# MCU.net
KiCad netlist of a schematic drawn in Altium Designer
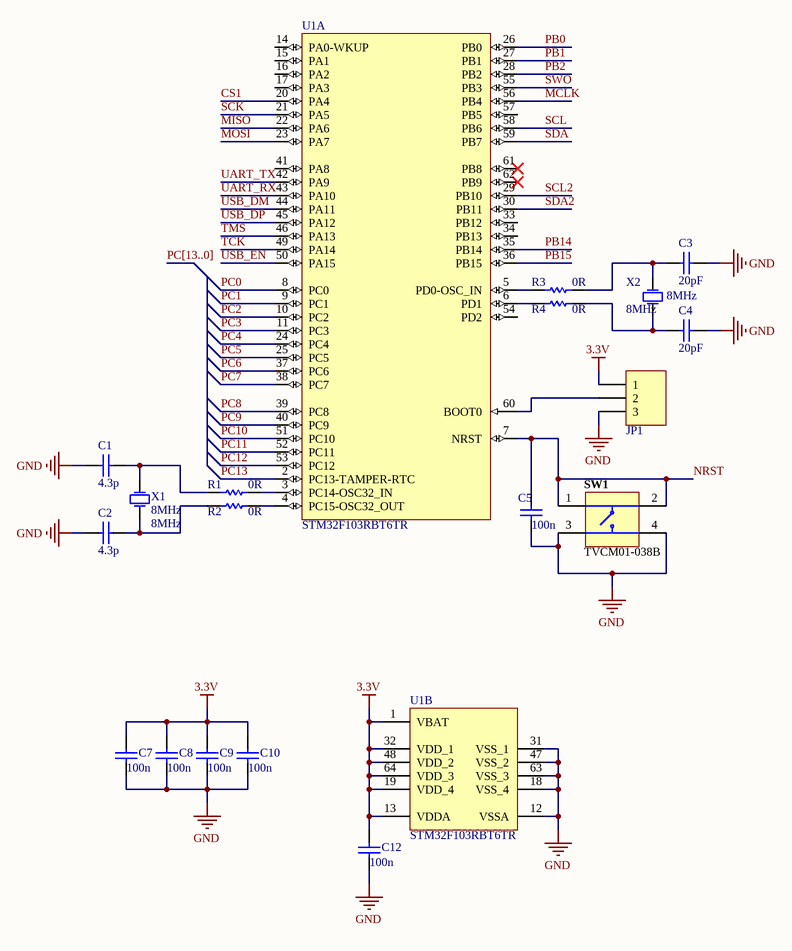
[diagram p0: MCU.SchDoc]

(export (version "E")
  (design (tool "Eeschema 10.0.6"))
  (components
    (comp (ref "C1")
      (value "4.3p")
      (footprint "CAPC0603(1608)100_L")
      (description "0603 (1608 Metric) Chip Capacitor")
      (libsource (lib "Altium Content Vault") (part "CAP_5"))
    )
    (comp (ref "C2")
      (value "4.3p")
      (footprint "CAPC0603(1608)100_L")
      (description "0603 (1608 Metric) Chip Capacitor")
      (libsource (lib "Altium Content Vault") (part "CAP_5"))
    )
    (comp (ref "C3")
      (value "20pF")
      (footprint "CAPC0603(1608)100_L")
      (description "0603 (1608 Metric) Chip Capacitor")
      (libsource (lib "Altium Content Vault") (part "CAP_5"))
    )
    (comp (ref "C4")
      (value "20pF")
      (footprint "CAPC0603(1608)100_L")
      (description "0603 (1608 Metric) Chip Capacitor")
      (libsource (lib "Altium Content Vault") (part "CAP_5"))
    )
    (comp (ref "C5")
      (value "100n")
      (footprint "CAPC0603(1608)100_L")
      (description "0603 (1608 Metric) Chip Capacitor")
      (libsource (lib "Altium Content Vault") (part "CAP_5"))
    )
    (comp (ref "C7")
      (value "100n")
      (footprint "CAPC0603(1608)100_L")
      (description "0603 (1608 Metric) Chip Capacitor")
      (libsource (lib "Altium Content Vault") (part "CAP_5"))
    )
    (comp (ref "C8")
      (value "100n")
      (footprint "CAPC0603(1608)100_L")
      (description "0603 (1608 Metric) Chip Capacitor")
      (libsource (lib "Altium Content Vault") (part "CAP_5"))
    )
    (comp (ref "C9")
      (value "100n")
      (footprint "CAPC0603(1608)100_L")
      (description "0603 (1608 Metric) Chip Capacitor")
      (libsource (lib "Altium Content Vault") (part "CAP_5"))
    )
    (comp (ref "C10")
      (value "100n")
      (footprint "CAPC0603(1608)100_L")
      (description "0603 (1608 Metric) Chip Capacitor")
      (libsource (lib "Altium Content Vault") (part "CAP_5"))
    )
    (comp (ref "C12")
      (value "100n")
      (footprint "CAPC0603(1608)100_L")
      (description "0603 (1608 Metric) Chip Capacitor")
      (libsource (lib "Altium Content Vault") (part "CAP_5"))
    )
    (comp (ref "JP1")
      (value "HDR1X3")
      (footprint "HDR1X3")
      (description "Header, 3-Pin")
      (fields (field (name "PUBLISHER") "Altium Limited"))
      (libsource (lib "Library_Altium") (part "HDR1X3"))
    )
    (comp (ref "R1")
      (value "0R")
      (footprint "RESC0603(1608)_L")
      (description "0603 (1608 Metric) Chip Resistor")
      (libsource (lib "Altium Content Vault") (part "RES_3"))
    )
    (comp (ref "R2")
      (value "0R")
      (footprint "RESC0603(1608)_L")
      (description "0603 (1608 Metric) Chip Resistor")
      (libsource (lib "Altium Content Vault") (part "RES_3"))
    )
    (comp (ref "R3")
      (value "0R")
      (footprint "RESC0603(1608)_L")
      (description "0603 (1608 Metric) Chip Resistor")
      (libsource (lib "Altium Content Vault") (part "RES_3"))
    )
    (comp (ref "R4")
      (value "0R")
      (footprint "RESC0603(1608)_L")
      (description "0603 (1608 Metric) Chip Resistor")
      (libsource (lib "Altium Content Vault") (part "RES_3"))
    )
    (comp (ref "SW1")
      (value "TVCM01-038B")
      (footprint "JNFU-TVCM01-038B_V")
      (description "Switch, Push Button, 50 mA, 12V DC, SMD")
      (libsource (lib "Altium Content Vault") (part "JNFU-TVCM01-038B-4"))
    )
    (comp (ref "U1")
      (value "STM32F103RBT6TR")
      (footprint "LQFP64_N")
      (libsource (lib "Altium Content Vault") (part "MC-ARM-STM32F101-SQ64"))
    )
    (comp (ref "X1")
      (value "8MHz")
      (footprint "HC49/4H_SMX")
      (description "Oscillator")
      (fields (field (name "ALTIUM_VALUE") "8MHz"))
      (libsource (lib "Library_Altium") (part "XTAL"))
    )
    (comp (ref "X2")
      (value "8MHz")
      (footprint "HC49/4H_SMX")
      (description "Oscillator")
      (fields (field (name "ALTIUM_VALUE") "8MHz"))
      (libsource (lib "Library_Altium") (part "XTAL"))
    )
  )
  (nets
    (net (code "1") (name "/CS1") (class "Default")
      (node (ref "U1") (pin "20") (pinfunction "PA4_20") (pintype "bidirectional"))
    )
    (net (code "2") (name "/MCLK") (class "Default")
      (node (ref "U1") (pin "56") (pinfunction "PB4_56") (pintype "bidirectional"))
    )
    (net (code "3") (name "/MISO") (class "Default")
      (node (ref "U1") (pin "22") (pinfunction "PA6_22") (pintype "bidirectional"))
    )
    (net (code "4") (name "/MOSI") (class "Default")
      (node (ref "U1") (pin "23") (pinfunction "PA7_23") (pintype "bidirectional"))
    )
    (net (code "5") (name "/NRST") (class "Default")
      (node (ref "C5") (pin "1") (pinfunction "1_1") (pintype "passive"))
      (node (ref "SW1") (pin "1") (pinfunction "1_1") (pintype "passive"))
      (node (ref "SW1") (pin "2") (pinfunction "2_2") (pintype "passive"))
      (node (ref "U1") (pin "7") (pinfunction "NRST_7") (pintype "bidirectional"))
    )
    (net (code "6") (name "/PB0") (class "Default")
      (node (ref "U1") (pin "26") (pinfunction "PB0_26") (pintype "bidirectional"))
    )
    (net (code "7") (name "/PB1") (class "Default")
      (node (ref "U1") (pin "27") (pinfunction "PB1_27") (pintype "bidirectional"))
    )
    (net (code "8") (name "/PB2") (class "Default")
      (node (ref "U1") (pin "28") (pinfunction "PB2_28") (pintype "bidirectional"))
    )
    (net (code "9") (name "/PB14") (class "Default")
      (node (ref "U1") (pin "35") (pinfunction "PB14_35") (pintype "bidirectional"))
    )
    (net (code "10") (name "/PB15") (class "Default")
      (node (ref "U1") (pin "36") (pinfunction "PB15_36") (pintype "bidirectional"))
    )
    (net (code "11") (name "/PC0") (class "Default")
      (node (ref "U1") (pin "8") (pinfunction "PC0_8") (pintype "bidirectional"))
    )
    (net (code "12") (name "/PC1") (class "Default")
      (node (ref "U1") (pin "9") (pinfunction "PC1_9") (pintype "bidirectional"))
    )
    (net (code "13") (name "/PC2") (class "Default")
      (node (ref "U1") (pin "10") (pinfunction "PC2_10") (pintype "bidirectional"))
    )
    (net (code "14") (name "/PC3") (class "Default")
      (node (ref "U1") (pin "11") (pinfunction "PC3_11") (pintype "bidirectional"))
    )
    (net (code "15") (name "/PC4") (class "Default")
      (node (ref "U1") (pin "24") (pinfunction "PC4_24") (pintype "bidirectional"))
    )
    (net (code "16") (name "/PC5") (class "Default")
      (node (ref "U1") (pin "25") (pinfunction "PC5_25") (pintype "bidirectional"))
    )
    (net (code "17") (name "/PC6") (class "Default")
      (node (ref "U1") (pin "37") (pinfunction "PC6_37") (pintype "bidirectional"))
    )
    (net (code "18") (name "/PC7") (class "Default")
      (node (ref "U1") (pin "38") (pinfunction "PC7_38") (pintype "bidirectional"))
    )
    (net (code "19") (name "/PC8") (class "Default")
      (node (ref "U1") (pin "39") (pinfunction "PC8_39") (pintype "bidirectional"))
    )
    (net (code "20") (name "/PC9") (class "Default")
      (node (ref "U1") (pin "40") (pinfunction "PC9_40") (pintype "bidirectional"))
    )
    (net (code "21") (name "/PC10") (class "Default")
      (node (ref "U1") (pin "51") (pinfunction "PC10_51") (pintype "bidirectional"))
    )
    (net (code "22") (name "/PC11") (class "Default")
      (node (ref "U1") (pin "52") (pinfunction "PC11_52") (pintype "bidirectional"))
    )
    (net (code "23") (name "/PC12") (class "Default")
      (node (ref "U1") (pin "53") (pinfunction "PC12_53") (pintype "bidirectional"))
    )
    (net (code "24") (name "/PC13") (class "Default")
      (node (ref "U1") (pin "2") (pinfunction "PC13-TAMPER-RTC_2") (pintype "bidirectional"))
    )
    (net (code "26") (name "/SCK") (class "Default")
      (node (ref "U1") (pin "21") (pinfunction "PA5_21") (pintype "bidirectional"))
    )
    (net (code "27") (name "/SCL") (class "Default")
      (node (ref "U1") (pin "58") (pinfunction "PB6_58") (pintype "bidirectional"))
    )
    (net (code "28") (name "/SCL2") (class "Default")
      (node (ref "U1") (pin "29") (pinfunction "PB10_29") (pintype "bidirectional"))
    )
    (net (code "29") (name "/SDA") (class "Default")
      (node (ref "U1") (pin "59") (pinfunction "PB7_59") (pintype "bidirectional"))
    )
    (net (code "30") (name "/SDA2") (class "Default")
      (node (ref "U1") (pin "30") (pinfunction "PB11_30") (pintype "bidirectional"))
    )
    (net (code "31") (name "/SWO") (class "Default")
      (node (ref "U1") (pin "55") (pinfunction "PB3_55") (pintype "bidirectional"))
    )
    (net (code "32") (name "/TCK") (class "Default")
      (node (ref "U1") (pin "49") (pinfunction "PA14_49") (pintype "bidirectional"))
    )
    (net (code "33") (name "/TMS") (class "Default")
      (node (ref "U1") (pin "46") (pinfunction "PA13_46") (pintype "bidirectional"))
    )
    (net (code "34") (name "/UART_RX") (class "Default")
      (node (ref "U1") (pin "43") (pinfunction "PA10_43") (pintype "bidirectional"))
    )
    (net (code "35") (name "/UART_TX") (class "Default")
      (node (ref "U1") (pin "42") (pinfunction "PA9_42") (pintype "bidirectional"))
    )
    (net (code "36") (name "/USB_DM") (class "Default")
      (node (ref "U1") (pin "44") (pinfunction "PA11_44") (pintype "bidirectional"))
    )
    (net (code "37") (name "/USB_DP") (class "Default")
      (node (ref "U1") (pin "45") (pinfunction "PA12_45") (pintype "bidirectional"))
    )
    (net (code "38") (name "/USB_EN") (class "Default")
      (node (ref "U1") (pin "50") (pinfunction "PA15_50") (pintype "bidirectional"))
    )
    (net (code "39") (name "3.3V") (class "Default")
      (node (ref "C10") (pin "2") (pinfunction "2_2") (pintype "passive"))
      (node (ref "C12") (pin "2") (pinfunction "2_2") (pintype "passive"))
      (node (ref "C7") (pin "2") (pinfunction "2_2") (pintype "passive"))
      (node (ref "C8") (pin "2") (pinfunction "2_2") (pintype "passive"))
      (node (ref "C9") (pin "2") (pinfunction "2_2") (pintype "passive"))
      (node (ref "JP1") (pin "1") (pinfunction "1_1") (pintype "passive"))
      (node (ref "U1") (pin "1") (pinfunction "VBAT_1") (pintype "power_in"))
      (node (ref "U1") (pin "13") (pinfunction "VDDA_13") (pintype "power_in"))
      (node (ref "U1") (pin "19") (pinfunction "VDD_4_19") (pintype "power_in"))
      (node (ref "U1") (pin "32") (pinfunction "VDD_1_32") (pintype "power_in"))
      (node (ref "U1") (pin "48") (pinfunction "VDD_2_48") (pintype "power_in"))
      (node (ref "U1") (pin "64") (pinfunction "VDD_3_64") (pintype "power_in"))
    )
    (net (code "40") (name "GND") (class "Default")
      (node (ref "C1") (pin "1") (pinfunction "1_1") (pintype "passive"))
      (node (ref "C10") (pin "1") (pinfunction "1_1") (pintype "passive"))
      (node (ref "C12") (pin "1") (pinfunction "1_1") (pintype "passive"))
      (node (ref "C2") (pin "1") (pinfunction "1_1") (pintype "passive"))
      (node (ref "C3") (pin "1") (pinfunction "1_1") (pintype "passive"))
      (node (ref "C4") (pin "1") (pinfunction "1_1") (pintype "passive"))
      (node (ref "C5") (pin "2") (pinfunction "2_2") (pintype "passive"))
      (node (ref "C7") (pin "1") (pinfunction "1_1") (pintype "passive"))
      (node (ref "C8") (pin "1") (pinfunction "1_1") (pintype "passive"))
      (node (ref "C9") (pin "1") (pinfunction "1_1") (pintype "passive"))
      (node (ref "JP1") (pin "3") (pinfunction "3_3") (pintype "passive"))
      (node (ref "SW1") (pin "3") (pinfunction "3_3") (pintype "passive"))
      (node (ref "SW1") (pin "4") (pinfunction "4_4") (pintype "passive"))
      (node (ref "U1") (pin "12") (pinfunction "VSSA_12") (pintype "power_in"))
      (node (ref "U1") (pin "18") (pinfunction "VSS_4_18") (pintype "power_in"))
      (node (ref "U1") (pin "31") (pinfunction "VSS_1_31") (pintype "power_in"))
      (node (ref "U1") (pin "47") (pinfunction "VSS_2_47") (pintype "power_in"))
      (node (ref "U1") (pin "63") (pinfunction "VSS_3_63") (pintype "power_in"))
    )
    (net (code "41") (name "Net-(U1A-BOOT0)") (class "Default")
      (node (ref "JP1") (pin "2") (pinfunction "2_2") (pintype "passive"))
      (node (ref "U1") (pin "60") (pinfunction "BOOT0_60") (pintype "input"))
    )
    (net (code "42") (name "Net-(U1A-PC14-OSC32_IN)") (class "Default")
      (node (ref "R1") (pin "2") (pinfunction "2_2") (pintype "passive"))
      (node (ref "U1") (pin "3") (pinfunction "PC14-OSC32_IN_3") (pintype "bidirectional"))
    )
    (net (code "43") (name "Net-(U1A-PC15-OSC32_OUT)") (class "Default")
      (node (ref "R2") (pin "2") (pinfunction "2_2") (pintype "passive"))
      (node (ref "U1") (pin "4") (pinfunction "PC15-OSC32_OUT_4") (pintype "bidirectional"))
    )
    (net (code "44") (name "Net-(U1A-PD0-OSC_IN)") (class "Default")
      (node (ref "R3") (pin "2") (pinfunction "2_2") (pintype "passive"))
      (node (ref "U1") (pin "5") (pinfunction "PD0-OSC_IN_5") (pintype "bidirectional"))
    )
    (net (code "45") (name "Net-(U1A-PD1)") (class "Default")
      (node (ref "R4") (pin "2") (pinfunction "2_2") (pintype "passive"))
      (node (ref "U1") (pin "6") (pinfunction "PD1_6") (pintype "bidirectional"))
    )
    (net (code "46") (name "Net-(X1-OSC1)") (class "Default")
      (node (ref "C2") (pin "2") (pinfunction "2_2") (pintype "passive"))
      (node (ref "R2") (pin "1") (pinfunction "1_1") (pintype "passive"))
      (node (ref "X1") (pin "1") (pinfunction "OSC1_1") (pintype "passive"))
    )
    (net (code "47") (name "Net-(X1-OSC2)") (class "Default")
      (node (ref "C1") (pin "2") (pinfunction "2_2") (pintype "passive"))
      (node (ref "R1") (pin "1") (pinfunction "1_1") (pintype "passive"))
      (node (ref "X1") (pin "2") (pinfunction "OSC2_2") (pintype "passive"))
    )
    (net (code "48") (name "Net-(X2-OSC1)") (class "Default")
      (node (ref "C3") (pin "2") (pinfunction "2_2") (pintype "passive"))
      (node (ref "R3") (pin "1") (pinfunction "1_1") (pintype "passive"))
      (node (ref "X2") (pin "1") (pinfunction "OSC1_1") (pintype "passive"))
    )
    (net (code "49") (name "Net-(X2-OSC2)") (class "Default")
      (node (ref "C4") (pin "2") (pinfunction "2_2") (pintype "passive"))
      (node (ref "R4") (pin "1") (pinfunction "1_1") (pintype "passive"))
      (node (ref "X2") (pin "2") (pinfunction "OSC2_2") (pintype "passive"))
    )
    (net (code "50") (name "unconnected-(U1A-PA0-WKUP-Pad14)") (class "Default")
      (node (ref "U1") (pin "14") (pinfunction "PA0-WKUP_14") (pintype "bidirectional"))
    )
    (net (code "51") (name "unconnected-(U1A-PA1-Pad15)") (class "Default")
      (node (ref "U1") (pin "15") (pinfunction "PA1_15") (pintype "bidirectional"))
    )
    (net (code "52") (name "unconnected-(U1A-PA2-Pad16)") (class "Default")
      (node (ref "U1") (pin "16") (pinfunction "PA2_16") (pintype "bidirectional"))
    )
    (net (code "53") (name "unconnected-(U1A-PA3-Pad17)") (class "Default")
      (node (ref "U1") (pin "17") (pinfunction "PA3_17") (pintype "bidirectional"))
    )
    (net (code "54") (name "unconnected-(U1A-PA8-Pad41)") (class "Default")
      (node (ref "U1") (pin "41") (pinfunction "PA8_41") (pintype "bidirectional"))
    )
    (net (code "55") (name "unconnected-(U1A-PB5-Pad57)") (class "Default")
      (node (ref "U1") (pin "57") (pinfunction "PB5_57") (pintype "bidirectional"))
    )
    (net (code "56") (name "unconnected-(U1A-PB8-Pad61)") (class "Default")
      (node (ref "U1") (pin "61") (pinfunction "PB8_61") (pintype "bidirectional+no_connect"))
    )
    (net (code "57") (name "unconnected-(U1A-PB9-Pad62)") (class "Default")
      (node (ref "U1") (pin "62") (pinfunction "PB9_62") (pintype "bidirectional+no_connect"))
    )
    (net (code "58") (name "unconnected-(U1A-PB12-Pad33)") (class "Default")
      (node (ref "U1") (pin "33") (pinfunction "PB12_33") (pintype "bidirectional"))
    )
    (net (code "59") (name "unconnected-(U1A-PB13-Pad34)") (class "Default")
      (node (ref "U1") (pin "34") (pinfunction "PB13_34") (pintype "bidirectional"))
    )
    (net (code "60") (name "unconnected-(U1A-PD2-Pad54)") (class "Default")
      (node (ref "U1") (pin "54") (pinfunction "PD2_54") (pintype "bidirectional"))
    )
  )
)
